# picprog.net
KiCad netlist of a schematic drawn in EAGLE
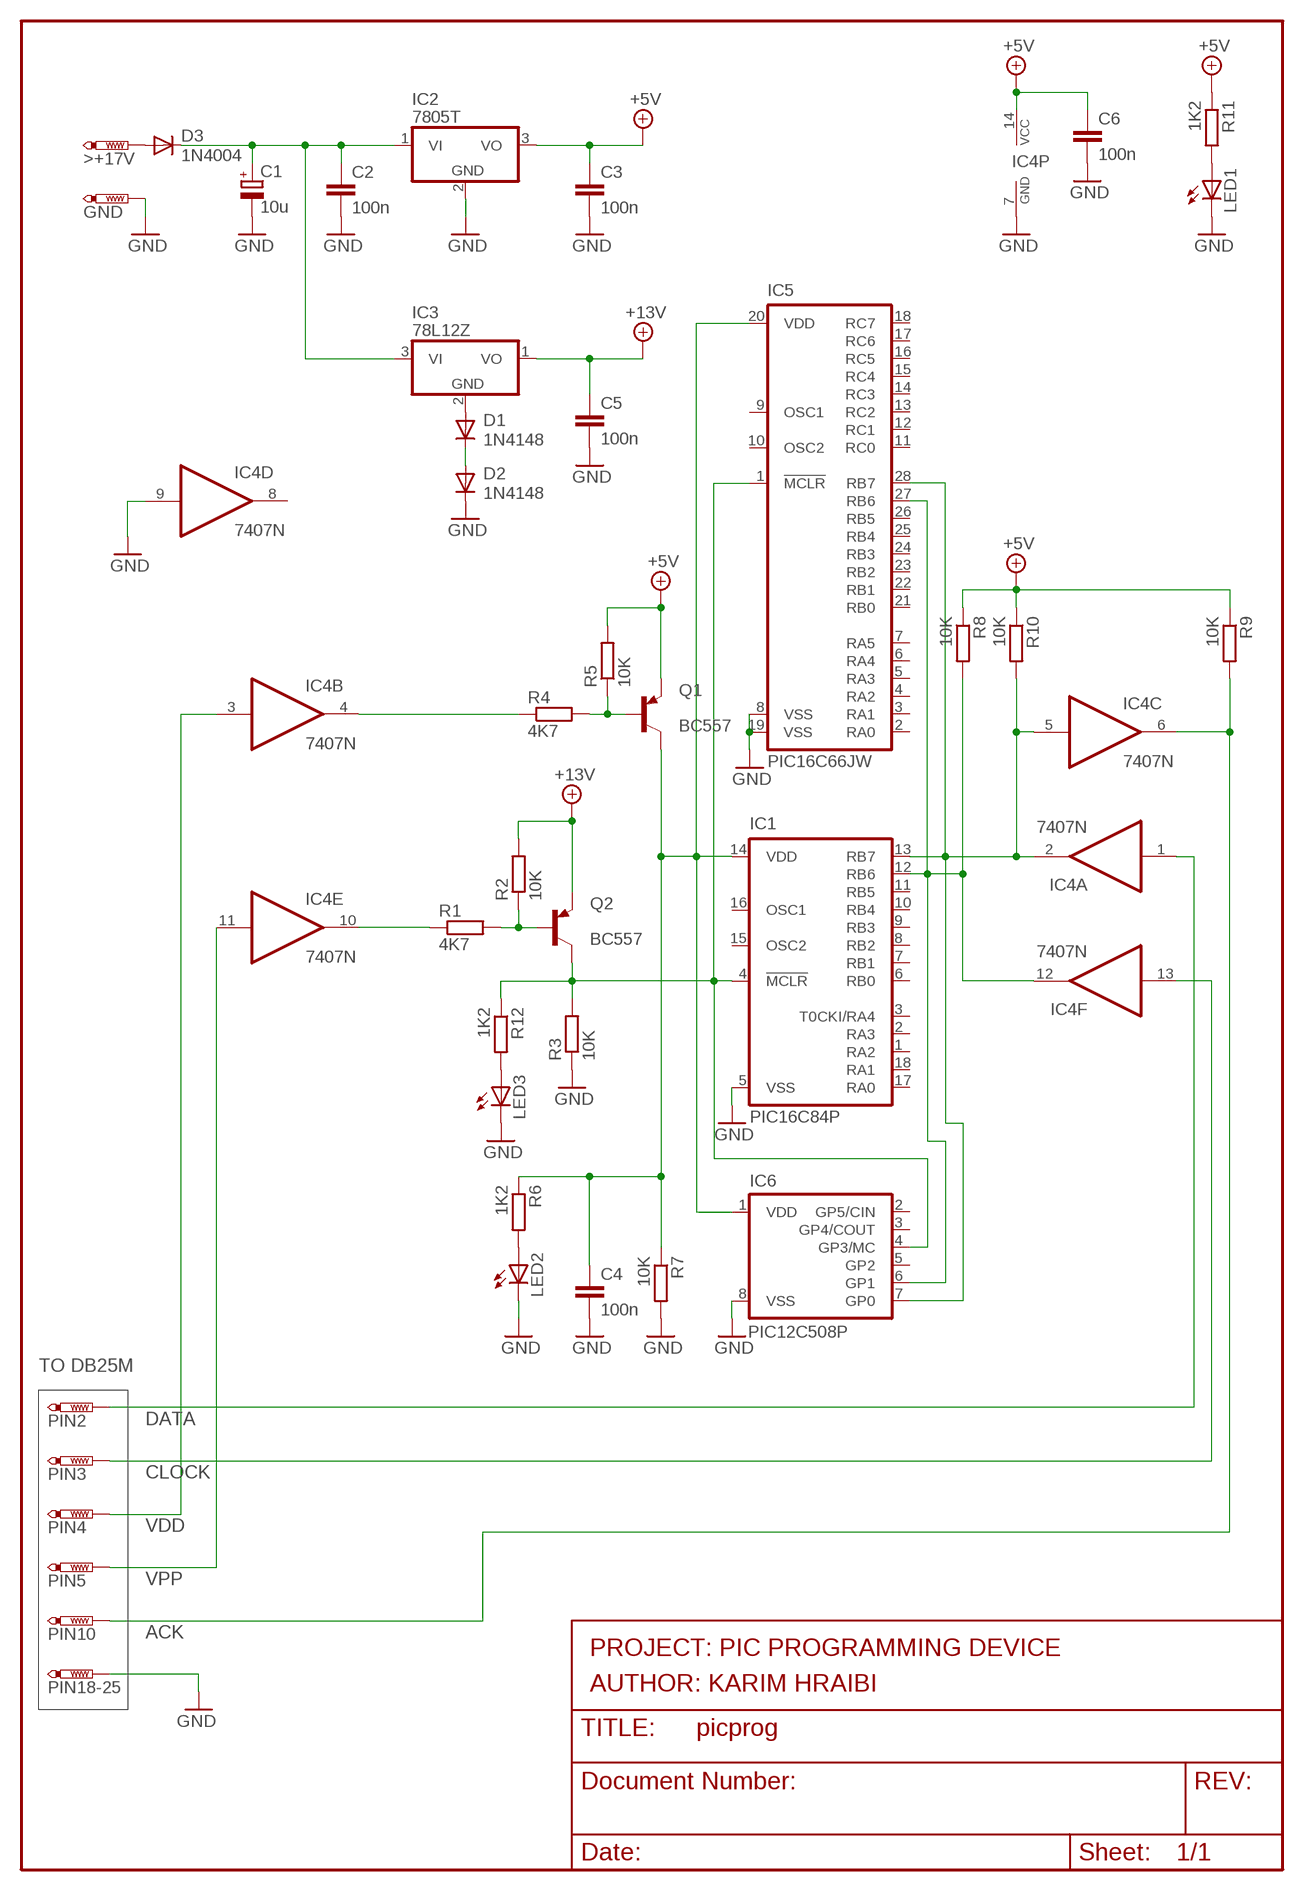
[diagram p0: schematic, sheet 1]

(export (version "E")
  (design (tool "Eeschema 10.0.6"))
  (components
    (comp (ref ">+17V")
      (value "PTR1PAD1")
      (footprint "eagle-import:P1")
      (libsource (lib "eagle-import") (part "PTR1PAD1"))
    )
    (comp (ref "C1")
      (value "10u")
      (footprint "eagle-import:E2,5-7")
      (libsource (lib "eagle-import") (part "CPOL-EUE2.5-7"))
    )
    (comp (ref "C2")
      (value "100n")
      (footprint "eagle-import:C025-025X050")
      (libsource (lib "eagle-import") (part "C-EU025-025X050"))
    )
    (comp (ref "C3")
      (value "100n")
      (footprint "eagle-import:C025-025X050")
      (libsource (lib "eagle-import") (part "C-EU025-025X050"))
    )
    (comp (ref "C4")
      (value "100n")
      (footprint "eagle-import:C025-025X050")
      (libsource (lib "eagle-import") (part "C-EU025-025X050"))
    )
    (comp (ref "C5")
      (value "100n")
      (footprint "eagle-import:C025-025X050")
      (libsource (lib "eagle-import") (part "C-EU025-025X050"))
    )
    (comp (ref "C6")
      (value "100n")
      (footprint "eagle-import:C025-025X050")
      (libsource (lib "eagle-import") (part "C-EU025-025X050"))
    )
    (comp (ref "D1")
      (value "1N4148")
      (footprint "eagle-import:DO35-10")
      (libsource (lib "eagle-import") (part "1N4148"))
    )
    (comp (ref "D2")
      (value "1N4148")
      (footprint "eagle-import:DO35-10")
      (libsource (lib "eagle-import") (part "1N4148"))
    )
    (comp (ref "D3")
      (value "1N4004")
      (footprint "eagle-import:DO41-10")
      (libsource (lib "eagle-import") (part "1N4004"))
    )
    (comp (ref "GND")
      (value "PTR1PAD1")
      (footprint "eagle-import:P1")
      (libsource (lib "eagle-import") (part "PTR1PAD1"))
    )
    (comp (ref "IC1")
      (value "PIC16C84P")
      (footprint "eagle-import:DIL18")
      (libsource (lib "eagle-import") (part "PIC16C84P"))
    )
    (comp (ref "IC2")
      (value "7805T")
      (footprint "eagle-import:TO220H")
      (libsource (lib "eagle-import") (part "78T05"))
    )
    (comp (ref "IC3")
      (value "78L12Z")
      (footprint "eagle-import:TO92")
      (libsource (lib "eagle-import") (part "78ZL12"))
    )
    (comp (ref "IC4")
      (value "7407N")
      (footprint "eagle-import:DIL14")
      (libsource (lib "eagle-import") (part "7407N"))
    )
    (comp (ref "IC5")
      (value "PIC16C66JW")
      (footprint "eagle-import:DIL28-6")
      (libsource (lib "eagle-import") (part "PIC16C66JW"))
    )
    (comp (ref "IC6")
      (value "PIC12C508P")
      (footprint "eagle-import:DIL8")
      (libsource (lib "eagle-import") (part "PIC12C?P508"))
    )
    (comp (ref "LED1")
      (value "LED5MM")
      (footprint "eagle-import:LED5MM")
      (libsource (lib "eagle-import") (part "LED5MM"))
    )
    (comp (ref "LED2")
      (value "LED5MM")
      (footprint "eagle-import:LED5MM")
      (libsource (lib "eagle-import") (part "LED5MM"))
    )
    (comp (ref "LED3")
      (value "LED5MM")
      (footprint "eagle-import:LED5MM")
      (libsource (lib "eagle-import") (part "LED5MM"))
    )
    (comp (ref "PIN2")
      (value "PTR1PAD1")
      (footprint "eagle-import:P1")
      (libsource (lib "eagle-import") (part "PTR1PAD1"))
    )
    (comp (ref "PIN3")
      (value "PTR1PAD1")
      (footprint "eagle-import:P1")
      (libsource (lib "eagle-import") (part "PTR1PAD1"))
    )
    (comp (ref "PIN4")
      (value "PTR1PAD1")
      (footprint "eagle-import:P1")
      (libsource (lib "eagle-import") (part "PTR1PAD1"))
    )
    (comp (ref "PIN5")
      (value "PTR1PAD1")
      (footprint "eagle-import:P1")
      (libsource (lib "eagle-import") (part "PTR1PAD1"))
    )
    (comp (ref "PIN10")
      (value "PTR1PAD1")
      (footprint "eagle-import:P1")
      (libsource (lib "eagle-import") (part "PTR1PAD1"))
    )
    (comp (ref "PIN18-25")
      (value "PTR1PAD1")
      (footprint "eagle-import:P1")
      (libsource (lib "eagle-import") (part "PTR1PAD1"))
    )
    (comp (ref "Q1")
      (value "BC557")
      (footprint "eagle-import:TO92")
      (libsource (lib "eagle-import") (part "BC327"))
    )
    (comp (ref "Q2")
      (value "BC557")
      (footprint "eagle-import:TO92")
      (libsource (lib "eagle-import") (part "BC327"))
    )
    (comp (ref "R1")
      (value "4K7")
      (footprint "eagle-import:0207_12")
      (libsource (lib "eagle-import") (part "R-EU_0207/12"))
    )
    (comp (ref "R2")
      (value "10K")
      (footprint "eagle-import:0207_12")
      (libsource (lib "eagle-import") (part "R-EU_0207/12"))
    )
    (comp (ref "R3")
      (value "10K")
      (footprint "eagle-import:0207_12")
      (libsource (lib "eagle-import") (part "R-EU_0207/12"))
    )
    (comp (ref "R4")
      (value "4K7")
      (footprint "eagle-import:0207_15")
      (libsource (lib "eagle-import") (part "R-EU_0207/15"))
    )
    (comp (ref "R5")
      (value "10K")
      (footprint "eagle-import:0207_12")
      (libsource (lib "eagle-import") (part "R-EU_0207/12"))
    )
    (comp (ref "R6")
      (value "1K2")
      (footprint "eagle-import:0207_12")
      (libsource (lib "eagle-import") (part "R-EU_0207/12"))
    )
    (comp (ref "R7")
      (value "10K")
      (footprint "eagle-import:0207_12")
      (libsource (lib "eagle-import") (part "R-EU_0207/12"))
    )
    (comp (ref "R8")
      (value "10K")
      (footprint "eagle-import:0207_12")
      (libsource (lib "eagle-import") (part "R-EU_0207/12"))
    )
    (comp (ref "R9")
      (value "10K")
      (footprint "eagle-import:0207_15")
      (libsource (lib "eagle-import") (part "R-EU_0207/15"))
    )
    (comp (ref "R10")
      (value "10K")
      (footprint "eagle-import:0207_12")
      (libsource (lib "eagle-import") (part "R-EU_0207/12"))
    )
    (comp (ref "R11")
      (value "1K2")
      (footprint "eagle-import:0207_12")
      (libsource (lib "eagle-import") (part "R-EU_0207/12"))
    )
    (comp (ref "R12")
      (value "1K2")
      (footprint "eagle-import:0207_12")
      (libsource (lib "eagle-import") (part "R-EU_0207/12"))
    )
  )
  (nets
    (net (code "1") (name "+5V") (class "Default")
      (node (ref "C3") (pin "1") (pinfunction "1_1") (pintype "passive"))
      (node (ref "C6") (pin "1") (pinfunction "1_1") (pintype "passive"))
      (node (ref "IC2") (pin "3") (pinfunction "VO_3") (pintype "passive"))
      (node (ref "IC4") (pin "14") (pinfunction "VCC_14") (pintype "power_in"))
      (node (ref "Q1") (pin "1") (pinfunction "E_1") (pintype "passive"))
      (node (ref "R10") (pin "1") (pinfunction "1_1") (pintype "passive"))
      (node (ref "R11") (pin "1") (pinfunction "1_1") (pintype "passive"))
      (node (ref "R5") (pin "2") (pinfunction "2_2") (pintype "passive"))
      (node (ref "R8") (pin "1") (pinfunction "1_1") (pintype "passive"))
      (node (ref "R9") (pin "1") (pinfunction "1_1") (pintype "passive"))
    )
    (net (code "2") (name "+13V") (class "Default")
      (node (ref "C5") (pin "1") (pinfunction "1_1") (pintype "passive"))
      (node (ref "IC3") (pin "1") (pinfunction "VO_1") (pintype "passive"))
      (node (ref "Q2") (pin "1") (pinfunction "E_1") (pintype "passive"))
      (node (ref "R2") (pin "2") (pinfunction "2_2") (pintype "passive"))
    )
    (net (code "3") (name "/ACK") (class "Default")
      (node (ref "IC4") (pin "6") (pinfunction "O_6") (pintype "open_collector"))
      (node (ref "PIN10") (pin "P$1") (pinfunction "TP_P$1") (pintype "input"))
      (node (ref "R9") (pin "2") (pinfunction "2_2") (pintype "passive"))
    )
    (net (code "4") (name "/CLOCK") (class "Default")
      (node (ref "IC4") (pin "13") (pinfunction "I_13") (pintype "input"))
      (node (ref "PIN3") (pin "P$1") (pinfunction "TP_P$1") (pintype "input"))
    )
    (net (code "5") (name "/DATA") (class "Default")
      (node (ref "IC4") (pin "1") (pinfunction "I_1") (pintype "input"))
      (node (ref "PIN2") (pin "P$1") (pinfunction "TP_P$1") (pintype "input"))
    )
    (net (code "6") (name "/VDD") (class "Default")
      (node (ref "IC4") (pin "3") (pinfunction "I_3") (pintype "input"))
      (node (ref "PIN4") (pin "P$1") (pinfunction "TP_P$1") (pintype "input"))
    )
    (net (code "7") (name "/VPP") (class "Default")
      (node (ref "IC4") (pin "11") (pinfunction "I_11") (pintype "input"))
      (node (ref "PIN5") (pin "P$1") (pinfunction "TP_P$1") (pintype "input"))
    )
    (net (code "8") (name "GND") (class "Default")
      (node (ref "C1") (pin "-") (pinfunction "-_-") (pintype "passive"))
      (node (ref "C2") (pin "2") (pinfunction "2_2") (pintype "passive"))
      (node (ref "C3") (pin "2") (pinfunction "2_2") (pintype "passive"))
      (node (ref "C4") (pin "2") (pinfunction "2_2") (pintype "passive"))
      (node (ref "C5") (pin "2") (pinfunction "2_2") (pintype "passive"))
      (node (ref "C6") (pin "2") (pinfunction "2_2") (pintype "passive"))
      (node (ref "D2") (pin "C") (pinfunction "C_C") (pintype "passive"))
      (node (ref "GND") (pin "P$1") (pinfunction "TP_P$1") (pintype "input"))
      (node (ref "IC1") (pin "5") (pinfunction "VSS_5") (pintype "power_in"))
      (node (ref "IC2") (pin "2") (pinfunction "GND_2") (pintype "passive"))
      (node (ref "IC4") (pin "7") (pinfunction "GND_7") (pintype "power_in"))
      (node (ref "IC4") (pin "9") (pinfunction "I_9") (pintype "input"))
      (node (ref "IC5") (pin "19") (pinfunction "VSS_19") (pintype "power_in"))
      (node (ref "IC5") (pin "8") (pinfunction "VSS_8") (pintype "power_in"))
      (node (ref "IC6") (pin "8") (pinfunction "VSS_8") (pintype "power_in"))
      (node (ref "LED1") (pin "K") (pinfunction "C_K") (pintype "passive"))
      (node (ref "LED2") (pin "K") (pinfunction "C_K") (pintype "passive"))
      (node (ref "LED3") (pin "K") (pinfunction "C_K") (pintype "passive"))
      (node (ref "PIN18-25") (pin "P$1") (pinfunction "TP_P$1") (pintype "input"))
      (node (ref "R3") (pin "1") (pinfunction "1_1") (pintype "passive"))
      (node (ref "R7") (pin "2") (pinfunction "2_2") (pintype "passive"))
    )
    (net (code "9") (name "Net-(>+17V-TP)") (class "Default")
      (node (ref ">+17V") (pin "P$1") (pinfunction "TP_P$1") (pintype "input"))
      (node (ref "D3") (pin "A") (pinfunction "A_A") (pintype "passive"))
    )
    (net (code "10") (name "Net-(D1-PadC)") (class "Default")
      (node (ref "D1") (pin "C") (pinfunction "C_C") (pintype "passive"))
      (node (ref "D2") (pin "A") (pinfunction "A_A") (pintype "passive"))
    )
    (net (code "11") (name "Net-(IC1-RB6)") (class "Default")
      (node (ref "IC1") (pin "12") (pinfunction "RB6_12") (pintype "bidirectional"))
      (node (ref "IC4") (pin "12") (pinfunction "O_12") (pintype "open_collector"))
      (node (ref "IC5") (pin "27") (pinfunction "RB6_27") (pintype "bidirectional"))
      (node (ref "IC6") (pin "6") (pinfunction "GP1_6") (pintype "bidirectional"))
      (node (ref "R8") (pin "2") (pinfunction "2_2") (pintype "passive"))
    )
    (net (code "12") (name "Net-(IC1-RB7)") (class "Default")
      (node (ref "IC1") (pin "13") (pinfunction "RB7_13") (pintype "bidirectional"))
      (node (ref "IC4") (pin "2") (pinfunction "O_2") (pintype "open_collector"))
      (node (ref "IC4") (pin "5") (pinfunction "I_5") (pintype "input"))
      (node (ref "IC5") (pin "28") (pinfunction "RB7_28") (pintype "bidirectional"))
      (node (ref "IC6") (pin "7") (pinfunction "GP0_7") (pintype "bidirectional"))
      (node (ref "R10") (pin "2") (pinfunction "2_2") (pintype "passive"))
    )
    (net (code "13") (name "Net-(IC1-VDD)") (class "Default")
      (node (ref "C4") (pin "1") (pinfunction "1_1") (pintype "passive"))
      (node (ref "IC1") (pin "14") (pinfunction "VDD_14") (pintype "power_in"))
      (node (ref "IC5") (pin "20") (pinfunction "VDD_20") (pintype "power_in"))
      (node (ref "IC6") (pin "1") (pinfunction "VDD_1") (pintype "power_in"))
      (node (ref "Q1") (pin "3") (pinfunction "C_3") (pintype "passive"))
      (node (ref "R6") (pin "1") (pinfunction "1_1") (pintype "passive"))
      (node (ref "R7") (pin "1") (pinfunction "1_1") (pintype "passive"))
    )
    (net (code "14") (name "Net-(IC1-~{MCLR})") (class "Default")
      (node (ref "IC1") (pin "4") (pinfunction "~{MCLR}_4") (pintype "input"))
      (node (ref "IC5") (pin "1") (pinfunction "~{MCLR}_1") (pintype "input"))
      (node (ref "IC6") (pin "4") (pinfunction "GP3/MC_4") (pintype "input"))
      (node (ref "Q2") (pin "3") (pinfunction "C_3") (pintype "passive"))
      (node (ref "R12") (pin "1") (pinfunction "1_1") (pintype "passive"))
      (node (ref "R3") (pin "2") (pinfunction "2_2") (pintype "passive"))
    )
    (net (code "15") (name "Net-(IC2-VI)") (class "Default")
      (node (ref "C1") (pin "+") (pinfunction "+_+") (pintype "passive"))
      (node (ref "C2") (pin "1") (pinfunction "1_1") (pintype "passive"))
      (node (ref "D3") (pin "C") (pinfunction "C_C") (pintype "passive"))
      (node (ref "IC2") (pin "1") (pinfunction "VI_1") (pintype "input"))
      (node (ref "IC3") (pin "3") (pinfunction "VI_3") (pintype "input"))
    )
    (net (code "16") (name "Net-(IC3-GND)") (class "Default")
      (node (ref "D1") (pin "A") (pinfunction "A_A") (pintype "passive"))
      (node (ref "IC3") (pin "2") (pinfunction "GND_2") (pintype "passive"))
    )
    (net (code "17") (name "Net-(IC4B-O)") (class "Default")
      (node (ref "IC4") (pin "4") (pinfunction "O_4") (pintype "open_collector"))
      (node (ref "R4") (pin "1") (pinfunction "1_1") (pintype "passive"))
    )
    (net (code "18") (name "Net-(IC4E-O)") (class "Default")
      (node (ref "IC4") (pin "10") (pinfunction "O_10") (pintype "open_collector"))
      (node (ref "R1") (pin "1") (pinfunction "1_1") (pintype "passive"))
    )
    (net (code "19") (name "Net-(LED1-PadA)") (class "Default")
      (node (ref "LED1") (pin "A") (pinfunction "A_A") (pintype "passive"))
      (node (ref "R11") (pin "2") (pinfunction "2_2") (pintype "passive"))
    )
    (net (code "20") (name "Net-(LED2-PadA)") (class "Default")
      (node (ref "LED2") (pin "A") (pinfunction "A_A") (pintype "passive"))
      (node (ref "R6") (pin "2") (pinfunction "2_2") (pintype "passive"))
    )
    (net (code "21") (name "Net-(LED3-PadA)") (class "Default")
      (node (ref "LED3") (pin "A") (pinfunction "A_A") (pintype "passive"))
      (node (ref "R12") (pin "2") (pinfunction "2_2") (pintype "passive"))
    )
    (net (code "22") (name "Net-(Q1-B)") (class "Default")
      (node (ref "Q1") (pin "2") (pinfunction "B_2") (pintype "passive"))
      (node (ref "R4") (pin "2") (pinfunction "2_2") (pintype "passive"))
      (node (ref "R5") (pin "1") (pinfunction "1_1") (pintype "passive"))
    )
    (net (code "23") (name "Net-(Q2-B)") (class "Default")
      (node (ref "Q2") (pin "2") (pinfunction "B_2") (pintype "passive"))
      (node (ref "R1") (pin "2") (pinfunction "2_2") (pintype "passive"))
      (node (ref "R2") (pin "1") (pinfunction "1_1") (pintype "passive"))
    )
    (net (code "24") (name "unconnected-(IC1-OSC1-Pad16)") (class "Default")
      (node (ref "IC1") (pin "16") (pinfunction "OSC1_16") (pintype "input"))
    )
    (net (code "25") (name "unconnected-(IC1-OSC2-Pad15)") (class "Default")
      (node (ref "IC1") (pin "15") (pinfunction "OSC2_15") (pintype "output"))
    )
    (net (code "26") (name "unconnected-(IC1-RA0-Pad17)") (class "Default")
      (node (ref "IC1") (pin "17") (pinfunction "RA0_17") (pintype "bidirectional"))
    )
    (net (code "27") (name "unconnected-(IC1-RA1-Pad18)") (class "Default")
      (node (ref "IC1") (pin "18") (pinfunction "RA1_18") (pintype "bidirectional"))
    )
    (net (code "28") (name "unconnected-(IC1-RA2-Pad1)") (class "Default")
      (node (ref "IC1") (pin "1") (pinfunction "RA2_1") (pintype "bidirectional"))
    )
    (net (code "29") (name "unconnected-(IC1-RA3-Pad2)") (class "Default")
      (node (ref "IC1") (pin "2") (pinfunction "RA3_2") (pintype "bidirectional"))
    )
    (net (code "30") (name "unconnected-(IC1-RB0-Pad6)") (class "Default")
      (node (ref "IC1") (pin "6") (pinfunction "RB0_6") (pintype "bidirectional"))
    )
    (net (code "31") (name "unconnected-(IC1-RB1-Pad7)") (class "Default")
      (node (ref "IC1") (pin "7") (pinfunction "RB1_7") (pintype "bidirectional"))
    )
    (net (code "32") (name "unconnected-(IC1-RB2-Pad8)") (class "Default")
      (node (ref "IC1") (pin "8") (pinfunction "RB2_8") (pintype "bidirectional"))
    )
    (net (code "33") (name "unconnected-(IC1-RB3-Pad9)") (class "Default")
      (node (ref "IC1") (pin "9") (pinfunction "RB3_9") (pintype "bidirectional"))
    )
    (net (code "34") (name "unconnected-(IC1-RB4-Pad10)") (class "Default")
      (node (ref "IC1") (pin "10") (pinfunction "RB4_10") (pintype "bidirectional"))
    )
    (net (code "35") (name "unconnected-(IC1-RB5-Pad11)") (class "Default")
      (node (ref "IC1") (pin "11") (pinfunction "RB5_11") (pintype "bidirectional"))
    )
    (net (code "36") (name "unconnected-(IC1-T0CKI{slash}RA4-Pad3)") (class "Default")
      (node (ref "IC1") (pin "3") (pinfunction "T0CKI/RA4_3") (pintype "bidirectional"))
    )
    (net (code "37") (name "unconnected-(IC4D-O-Pad8)") (class "Default")
      (node (ref "IC4") (pin "8") (pinfunction "O_8") (pintype "open_collector"))
    )
    (net (code "38") (name "unconnected-(IC5-OSC1-Pad9)") (class "Default")
      (node (ref "IC5") (pin "9") (pinfunction "OSC1_9") (pintype "bidirectional"))
    )
    (net (code "39") (name "unconnected-(IC5-OSC2-Pad10)") (class "Default")
      (node (ref "IC5") (pin "10") (pinfunction "OSC2_10") (pintype "bidirectional"))
    )
    (net (code "40") (name "unconnected-(IC5-RA0-Pad2)") (class "Default")
      (node (ref "IC5") (pin "2") (pinfunction "RA0_2") (pintype "bidirectional"))
    )
    (net (code "41") (name "unconnected-(IC5-RA1-Pad3)") (class "Default")
      (node (ref "IC5") (pin "3") (pinfunction "RA1_3") (pintype "bidirectional"))
    )
    (net (code "42") (name "unconnected-(IC5-RA2-Pad4)") (class "Default")
      (node (ref "IC5") (pin "4") (pinfunction "RA2_4") (pintype "bidirectional"))
    )
    (net (code "43") (name "unconnected-(IC5-RA3-Pad5)") (class "Default")
      (node (ref "IC5") (pin "5") (pinfunction "RA3_5") (pintype "bidirectional"))
    )
    (net (code "44") (name "unconnected-(IC5-RA4-Pad6)") (class "Default")
      (node (ref "IC5") (pin "6") (pinfunction "RA4_6") (pintype "bidirectional"))
    )
    (net (code "45") (name "unconnected-(IC5-RA5-Pad7)") (class "Default")
      (node (ref "IC5") (pin "7") (pinfunction "RA5_7") (pintype "bidirectional"))
    )
    (net (code "46") (name "unconnected-(IC5-RB0-Pad21)") (class "Default")
      (node (ref "IC5") (pin "21") (pinfunction "RB0_21") (pintype "bidirectional"))
    )
    (net (code "47") (name "unconnected-(IC5-RB1-Pad22)") (class "Default")
      (node (ref "IC5") (pin "22") (pinfunction "RB1_22") (pintype "bidirectional"))
    )
    (net (code "48") (name "unconnected-(IC5-RB2-Pad23)") (class "Default")
      (node (ref "IC5") (pin "23") (pinfunction "RB2_23") (pintype "bidirectional"))
    )
    (net (code "49") (name "unconnected-(IC5-RB3-Pad24)") (class "Default")
      (node (ref "IC5") (pin "24") (pinfunction "RB3_24") (pintype "bidirectional"))
    )
    (net (code "50") (name "unconnected-(IC5-RB4-Pad25)") (class "Default")
      (node (ref "IC5") (pin "25") (pinfunction "RB4_25") (pintype "bidirectional"))
    )
    (net (code "51") (name "unconnected-(IC5-RB5-Pad26)") (class "Default")
      (node (ref "IC5") (pin "26") (pinfunction "RB5_26") (pintype "bidirectional"))
    )
    (net (code "52") (name "unconnected-(IC5-RC0-Pad11)") (class "Default")
      (node (ref "IC5") (pin "11") (pinfunction "RC0_11") (pintype "bidirectional"))
    )
    (net (code "53") (name "unconnected-(IC5-RC1-Pad12)") (class "Default")
      (node (ref "IC5") (pin "12") (pinfunction "RC1_12") (pintype "bidirectional"))
    )
    (net (code "54") (name "unconnected-(IC5-RC2-Pad13)") (class "Default")
      (node (ref "IC5") (pin "13") (pinfunction "RC2_13") (pintype "bidirectional"))
    )
    (net (code "55") (name "unconnected-(IC5-RC3-Pad14)") (class "Default")
      (node (ref "IC5") (pin "14") (pinfunction "RC3_14") (pintype "bidirectional"))
    )
    (net (code "56") (name "unconnected-(IC5-RC4-Pad15)") (class "Default")
      (node (ref "IC5") (pin "15") (pinfunction "RC4_15") (pintype "bidirectional"))
    )
    (net (code "57") (name "unconnected-(IC5-RC5-Pad16)") (class "Default")
      (node (ref "IC5") (pin "16") (pinfunction "RC5_16") (pintype "bidirectional"))
    )
    (net (code "58") (name "unconnected-(IC5-RC6-Pad17)") (class "Default")
      (node (ref "IC5") (pin "17") (pinfunction "RC6_17") (pintype "bidirectional"))
    )
    (net (code "59") (name "unconnected-(IC5-RC7-Pad18)") (class "Default")
      (node (ref "IC5") (pin "18") (pinfunction "RC7_18") (pintype "bidirectional"))
    )
    (net (code "60") (name "unconnected-(IC6-GP2-Pad5)") (class "Default")
      (node (ref "IC6") (pin "5") (pinfunction "GP2_5") (pintype "bidirectional"))
    )
    (net (code "61") (name "unconnected-(IC6-GP4{slash}COUT-Pad3)") (class "Default")
      (node (ref "IC6") (pin "3") (pinfunction "GP4/COUT_3") (pintype "bidirectional"))
    )
    (net (code "62") (name "unconnected-(IC6-GP5{slash}CIN-Pad2)") (class "Default")
      (node (ref "IC6") (pin "2") (pinfunction "GP5/CIN_2") (pintype "bidirectional"))
    )
  )
)
